# smoker-pid-control.net
KiCad netlist of a schematic drawn in EAGLE
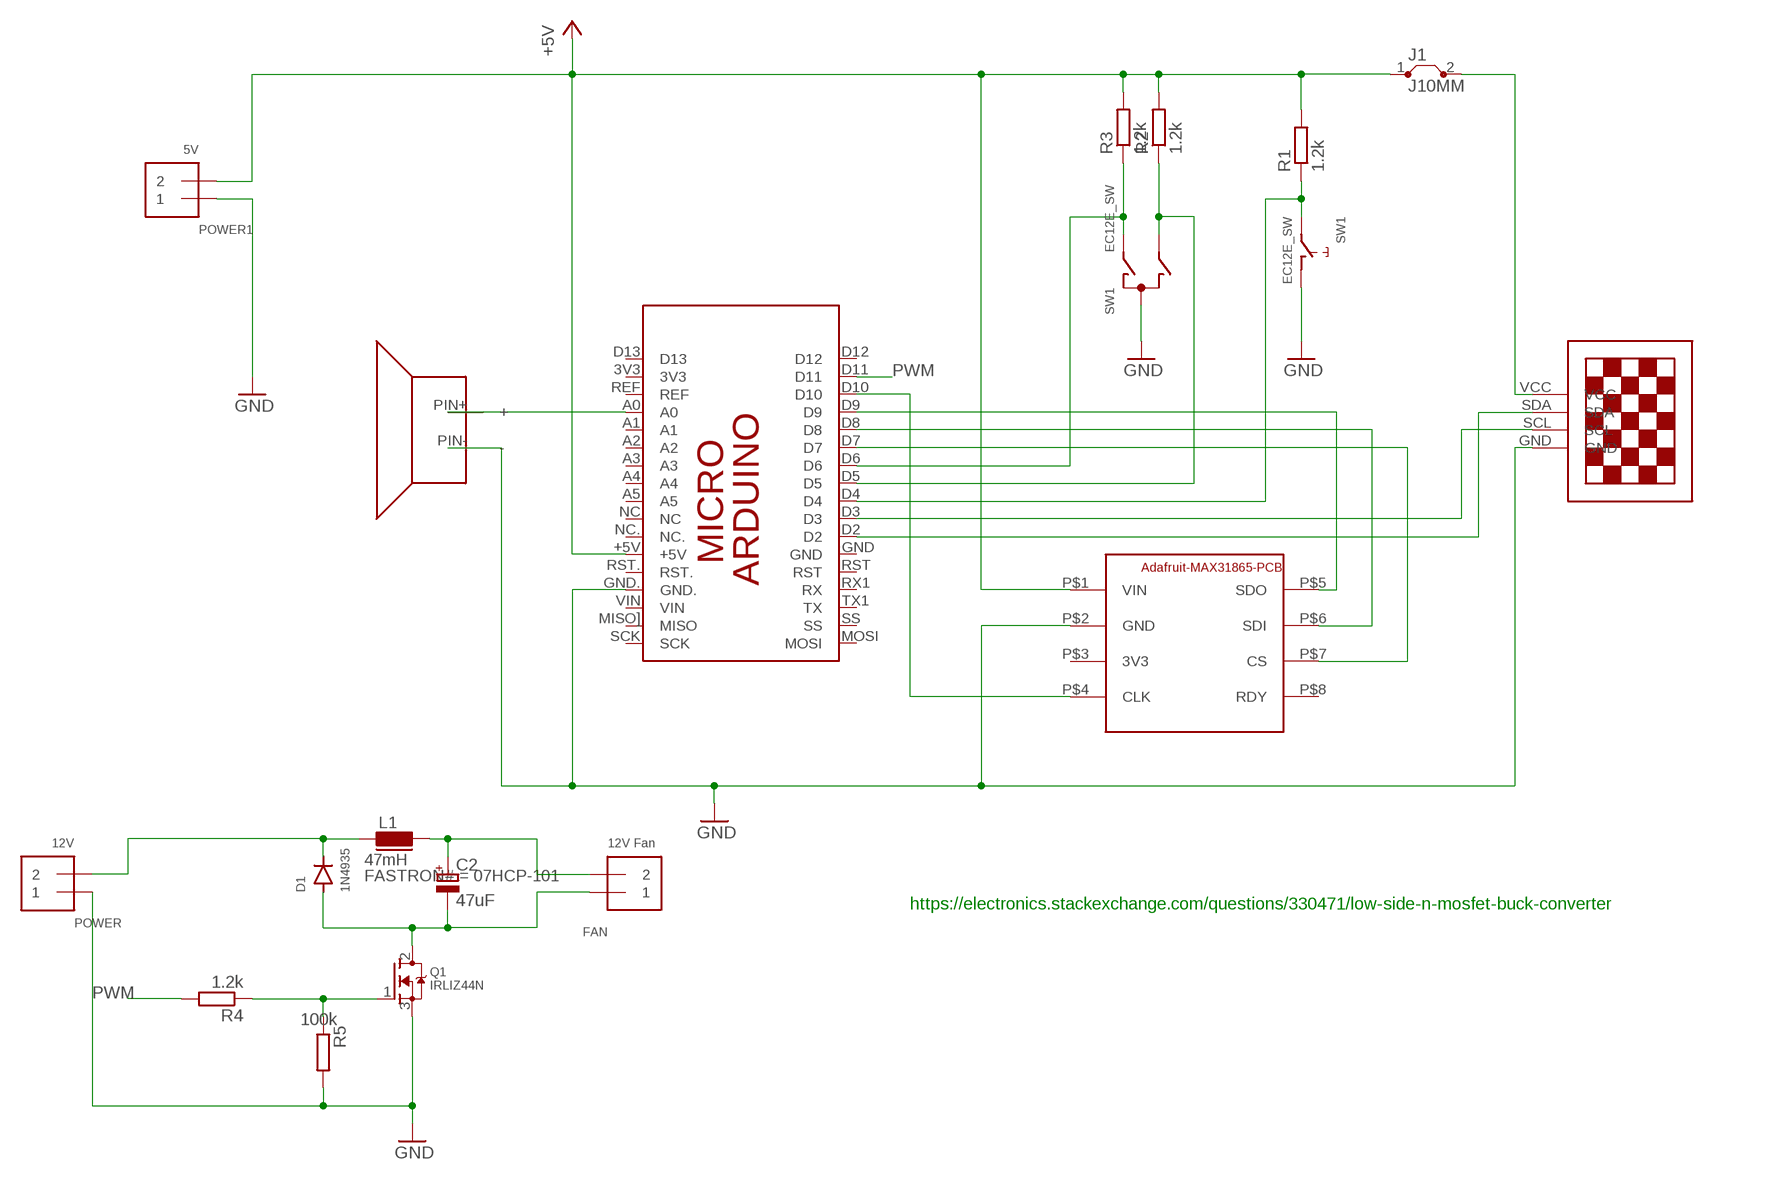
[diagram p0: schematic, sheet 1]

(export (version "E")
  (design (tool "Eeschema 10.0.6"))
  (components
    (comp (ref "C2")
      (value "47uF")
      (footprint "eagle-import:E5-8,5")
      (libsource (lib "eagle-import") (part "CPOL-EUE5-8.5"))
    )
    (comp (ref "D1")
      (value "1N4935")
      (footprint "eagle-import:DO34-7")
      (libsource (lib "eagle-import") (part "DIODE-DO34-7"))
    )
    (comp (ref "FAN")
      (value "12V Fan")
      (footprint "eagle-import:TERMBLOCK_1X2-3.5MM")
      (libsource (lib "eagle-import") (part "TERMBLOCK_1X2"))
    )
    (comp (ref "J1")
      (value "J10MM")
      (footprint "eagle-import:10")
      (libsource (lib "eagle-import") (part "J10MM"))
    )
    (comp (ref "L1")
      (value "47mH")
      (footprint "eagle-import:FASTRON_07HCP_INDUCTOR")
      (fields (field (name "FASTRON#") "07HCP-101"))
      (libsource (lib "eagle-import") (part "07HCP-100U"))
    )
    (comp (ref "PCB1")
      (value "ARDUINO_MICRO")
      (footprint "eagle-import:ARDUINO_MICRO")
      (libsource (lib "eagle-import") (part "ARDUINO_MICRO"))
    )
    (comp (ref "POWER")
      (value "12V")
      (footprint "eagle-import:TERMBLOCK_1X2-3.5MM")
      (libsource (lib "eagle-import") (part "TERMBLOCK_1X2"))
    )
    (comp (ref "POWER1")
      (value "5V")
      (footprint "eagle-import:TERMBLOCK_1X2-3.5MM")
      (libsource (lib "eagle-import") (part "TERMBLOCK_1X2"))
    )
    (comp (ref "Q1")
      (value "IRLIZ44N")
      (footprint "eagle-import:TO220V")
      (libsource (lib "eagle-import") (part "MOSFET-NGDS_TO220V"))
    )
    (comp (ref "R1")
      (value "1.2k")
      (footprint "eagle-import:0207_10")
      (libsource (lib "eagle-import") (part "R-EU_0207/10"))
    )
    (comp (ref "R2")
      (value "1.2k")
      (footprint "eagle-import:0207_15")
      (libsource (lib "eagle-import") (part "R-EU_0207/15"))
    )
    (comp (ref "R3")
      (value "1.2k")
      (footprint "eagle-import:0207_10")
      (libsource (lib "eagle-import") (part "R-EU_0207/10"))
    )
    (comp (ref "R4")
      (value "1.2k")
      (footprint "eagle-import:0207_10")
      (libsource (lib "eagle-import") (part "R-EU_0207/10"))
    )
    (comp (ref "R5")
      (value "100k")
      (footprint "eagle-import:0207_10")
      (libsource (lib "eagle-import") (part "R-EU_0207/10"))
    )
    (comp (ref "SW1")
      (value "EC12E_SW")
      (footprint "eagle-import:ALPS_EC12E_SW")
      (fields (field (name "MPN") "EC12E2424407"))
      (libsource (lib "eagle-import") (part "EC12E_SW"))
    )
    (comp (ref "U$1")
      (value "ADAFRUIT-MAX31865")
      (footprint "eagle-import:MAX31865-BRD")
      (libsource (lib "eagle-import") (part "ADAFRUIT-MAX31865"))
    )
    (comp (ref "U$2")
      (value "13\"OLED13\"OLED")
      (footprint "eagle-import:1.3_OLED")
      (libsource (lib "eagle-import") (part "13{dblquote}OLED13{dblquote}OLED"))
    )
    (comp (ref "U$3")
      (value "KC-1206")
      (footprint "eagle-import:KC-1206")
      (libsource (lib "eagle-import") (part "KC-1206"))
    )
  )
  (nets
    (net (code "1") (name "+5V") (class "Default")
      (node (ref "J1") (pin "1") (pinfunction "1_1") (pintype "passive"))
      (node (ref "PCB1") (pin "+5V") (pinfunction "+5V_+5V") (pintype "bidirectional"))
      (node (ref "POWER1") (pin "2") (pinfunction "2_2") (pintype "passive"))
      (node (ref "R1") (pin "2") (pinfunction "2_2") (pintype "passive"))
      (node (ref "R2") (pin "2") (pinfunction "2_2") (pintype "passive"))
      (node (ref "R3") (pin "2") (pinfunction "2_2") (pintype "passive"))
      (node (ref "U$1") (pin "P$1") (pinfunction "VIN_P$1") (pintype "power_in"))
    )
    (net (code "2") (name "/3V3") (class "Default")
      (node (ref "U$1") (pin "P$3") (pinfunction "3V3_P$3") (pintype "power_in"))
    )
    (net (code "3") (name "/PWM") (class "Default")
      (node (ref "PCB1") (pin "D11") (pinfunction "D11_D11") (pintype "bidirectional"))
      (node (ref "R4") (pin "2") (pinfunction "2_2") (pintype "passive"))
    )
    (net (code "4") (name "GND") (class "Default")
      (node (ref "PCB1") (pin "GND.") (pinfunction "GND._GND.") (pintype "bidirectional"))
      (node (ref "POWER") (pin "1") (pinfunction "1_1") (pintype "passive"))
      (node (ref "POWER1") (pin "1") (pinfunction "1_1") (pintype "passive"))
      (node (ref "Q1") (pin "3") (pinfunction "S_3") (pintype "bidirectional"))
      (node (ref "R5") (pin "2") (pinfunction "2_2") (pintype "passive"))
      (node (ref "SW1") (pin "C") (pinfunction "C_C") (pintype "passive"))
      (node (ref "SW1") (pin "D") (pinfunction "1_D") (pintype "passive"))
      (node (ref "U$1") (pin "P$2") (pinfunction "GND_P$2") (pintype "power_in"))
      (node (ref "U$2") (pin "GND") (pinfunction "GND_GND") (pintype "bidirectional"))
      (node (ref "U$3") (pin "PIN-") (pinfunction "-_PIN-") (pintype "bidirectional"))
    )
    (net (code "5") (name "Net-(C2-Pad+)") (class "Default")
      (node (ref "C2") (pin "+") (pinfunction "+_+") (pintype "passive"))
      (node (ref "FAN") (pin "2") (pinfunction "2_2") (pintype "passive"))
      (node (ref "L1") (pin "2") (pinfunction "2_2") (pintype "passive"))
    )
    (net (code "6") (name "Net-(D1-PadC)") (class "Default")
      (node (ref "D1") (pin "C") (pinfunction "C_C") (pintype "passive"))
      (node (ref "L1") (pin "1") (pinfunction "1_1") (pintype "passive"))
      (node (ref "POWER") (pin "2") (pinfunction "2_2") (pintype "passive"))
    )
    (net (code "7") (name "Net-(J1-Pad2)") (class "Default")
      (node (ref "J1") (pin "2") (pinfunction "2_2") (pintype "passive"))
      (node (ref "U$2") (pin "VCC") (pinfunction "VCC_VCC") (pintype "bidirectional"))
    )
    (net (code "8") (name "Net-(PCB1-PadD2)") (class "Default")
      (node (ref "PCB1") (pin "D2") (pinfunction "D2_D2") (pintype "bidirectional"))
      (node (ref "U$2") (pin "SDA") (pinfunction "SDA_SDA") (pintype "bidirectional"))
    )
    (net (code "9") (name "Net-(PCB1-PadD3)") (class "Default")
      (node (ref "PCB1") (pin "D3") (pinfunction "D3_D3") (pintype "bidirectional"))
      (node (ref "U$2") (pin "SCL") (pinfunction "SCL_SCL") (pintype "bidirectional"))
    )
    (net (code "10") (name "Net-(PCB1-PadD5)") (class "Default")
      (node (ref "PCB1") (pin "D5") (pinfunction "D5_D5") (pintype "bidirectional"))
      (node (ref "R2") (pin "1") (pinfunction "1_1") (pintype "passive"))
      (node (ref "SW1") (pin "B") (pinfunction "B_B") (pintype "passive"))
    )
    (net (code "11") (name "Net-(PCB1-PadD6)") (class "Default")
      (node (ref "PCB1") (pin "D6") (pinfunction "D6_D6") (pintype "bidirectional"))
      (node (ref "R3") (pin "1") (pinfunction "1_1") (pintype "passive"))
      (node (ref "SW1") (pin "A") (pinfunction "A_A") (pintype "passive"))
    )
    (net (code "12") (name "Net-(Q1-D)") (class "Default")
      (node (ref "C2") (pin "-") (pinfunction "-_-") (pintype "passive"))
      (node (ref "D1") (pin "A") (pinfunction "A_A") (pintype "passive"))
      (node (ref "FAN") (pin "1") (pinfunction "1_1") (pintype "passive"))
      (node (ref "Q1") (pin "2") (pinfunction "D_2") (pintype "bidirectional"))
    )
    (net (code "13") (name "Net-(Q1-G)") (class "Default")
      (node (ref "Q1") (pin "1") (pinfunction "G_1") (pintype "bidirectional"))
      (node (ref "R4") (pin "1") (pinfunction "1_1") (pintype "passive"))
      (node (ref "R5") (pin "1") (pinfunction "1_1") (pintype "passive"))
    )
    (net (code "14") (name "Net-(SW1B-2)") (class "Default")
      (node (ref "PCB1") (pin "D4") (pinfunction "D4_D4") (pintype "bidirectional"))
      (node (ref "R1") (pin "1") (pinfunction "1_1") (pintype "passive"))
      (node (ref "SW1") (pin "E") (pinfunction "2_E") (pintype "passive"))
    )
    (net (code "15") (name "Net-(U$1-CLK)") (class "Default")
      (node (ref "PCB1") (pin "D10") (pinfunction "D10_D10") (pintype "bidirectional"))
      (node (ref "U$1") (pin "P$4") (pinfunction "CLK_P$4") (pintype "bidirectional"))
    )
    (net (code "16") (name "Net-(U$1-CS)") (class "Default")
      (node (ref "PCB1") (pin "D7") (pinfunction "D7_D7") (pintype "bidirectional"))
      (node (ref "U$1") (pin "P$7") (pinfunction "CS_P$7") (pintype "bidirectional"))
    )
    (net (code "17") (name "Net-(U$1-SDI)") (class "Default")
      (node (ref "PCB1") (pin "D8") (pinfunction "D8_D8") (pintype "bidirectional"))
      (node (ref "U$1") (pin "P$6") (pinfunction "SDI_P$6") (pintype "bidirectional"))
    )
    (net (code "18") (name "Net-(U$1-SDO)") (class "Default")
      (node (ref "PCB1") (pin "D9") (pinfunction "D9_D9") (pintype "bidirectional"))
      (node (ref "U$1") (pin "P$5") (pinfunction "SDO_P$5") (pintype "bidirectional"))
    )
    (net (code "19") (name "Net-(U$3-+)") (class "Default")
      (node (ref "PCB1") (pin "A0") (pinfunction "A0_A0") (pintype "bidirectional"))
      (node (ref "U$3") (pin "PIN+") (pinfunction "+_PIN+") (pintype "power_in"))
    )
    (net (code "20") (name "unconnected-(PCB1-MISO-PadMISO])") (class "Default")
      (node (ref "PCB1") (pin "MISO]") (pinfunction "MISO_MISO]") (pintype "bidirectional"))
    )
    (net (code "21") (name "unconnected-(PCB1-Pad3V3)") (class "Default")
      (node (ref "PCB1") (pin "3V3") (pinfunction "3V3_3V3") (pintype "bidirectional"))
    )
    (net (code "22") (name "unconnected-(PCB1-PadA1)") (class "Default")
      (node (ref "PCB1") (pin "A1") (pinfunction "A1_A1") (pintype "bidirectional"))
    )
    (net (code "23") (name "unconnected-(PCB1-PadA2)") (class "Default")
      (node (ref "PCB1") (pin "A2") (pinfunction "A2_A2") (pintype "bidirectional"))
    )
    (net (code "24") (name "unconnected-(PCB1-PadA3)") (class "Default")
      (node (ref "PCB1") (pin "A3") (pinfunction "A3_A3") (pintype "bidirectional"))
    )
    (net (code "25") (name "unconnected-(PCB1-PadA4)") (class "Default")
      (node (ref "PCB1") (pin "A4") (pinfunction "A4_A4") (pintype "bidirectional"))
    )
    (net (code "26") (name "unconnected-(PCB1-PadA5)") (class "Default")
      (node (ref "PCB1") (pin "A5") (pinfunction "A5_A5") (pintype "bidirectional"))
    )
    (net (code "27") (name "unconnected-(PCB1-PadD12)") (class "Default")
      (node (ref "PCB1") (pin "D12") (pinfunction "D12_D12") (pintype "bidirectional"))
    )
    (net (code "28") (name "unconnected-(PCB1-PadD13)") (class "Default")
      (node (ref "PCB1") (pin "D13") (pinfunction "D13_D13") (pintype "bidirectional"))
    )
    (net (code "29") (name "unconnected-(PCB1-PadGND)") (class "Default")
      (node (ref "PCB1") (pin "GND") (pinfunction "GND_GND") (pintype "bidirectional"))
    )
    (net (code "30") (name "unconnected-(PCB1-PadMOSI)") (class "Default")
      (node (ref "PCB1") (pin "MOSI") (pinfunction "MOSI_MOSI") (pintype "bidirectional"))
    )
    (net (code "31") (name "unconnected-(PCB1-PadNC)") (class "Default")
      (node (ref "PCB1") (pin "NC") (pinfunction "NC_NC") (pintype "bidirectional"))
    )
    (net (code "32") (name "unconnected-(PCB1-PadNC.)") (class "Default")
      (node (ref "PCB1") (pin "NC.") (pinfunction "NC._NC.") (pintype "bidirectional"))
    )
    (net (code "33") (name "unconnected-(PCB1-PadREF)") (class "Default")
      (node (ref "PCB1") (pin "REF") (pinfunction "REF_REF") (pintype "bidirectional"))
    )
    (net (code "34") (name "unconnected-(PCB1-PadRST)") (class "Default")
      (node (ref "PCB1") (pin "RST") (pinfunction "RST_RST") (pintype "bidirectional"))
    )
    (net (code "35") (name "unconnected-(PCB1-PadRST.)") (class "Default")
      (node (ref "PCB1") (pin "RST.") (pinfunction "RST._RST.") (pintype "bidirectional"))
    )
    (net (code "36") (name "unconnected-(PCB1-PadSCK)") (class "Default")
      (node (ref "PCB1") (pin "SCK") (pinfunction "SCK_SCK") (pintype "bidirectional"))
    )
    (net (code "37") (name "unconnected-(PCB1-PadSS)") (class "Default")
      (node (ref "PCB1") (pin "SS") (pinfunction "SS_SS") (pintype "bidirectional"))
    )
    (net (code "38") (name "unconnected-(PCB1-PadVIN)") (class "Default")
      (node (ref "PCB1") (pin "VIN") (pinfunction "VIN_VIN") (pintype "bidirectional"))
    )
    (net (code "39") (name "unconnected-(PCB1-RX-PadRX1)") (class "Default")
      (node (ref "PCB1") (pin "RX1") (pinfunction "RX_RX1") (pintype "bidirectional"))
    )
    (net (code "40") (name "unconnected-(PCB1-TX-PadTX1)") (class "Default")
      (node (ref "PCB1") (pin "TX1") (pinfunction "TX_TX1") (pintype "bidirectional"))
    )
    (net (code "41") (name "unconnected-(U$1-RDY-PadP$8)") (class "Default")
      (node (ref "U$1") (pin "P$8") (pinfunction "RDY_P$8") (pintype "bidirectional"))
    )
  )
)
